# lab1.net
KiCad netlist of a schematic drawn in EAGLE
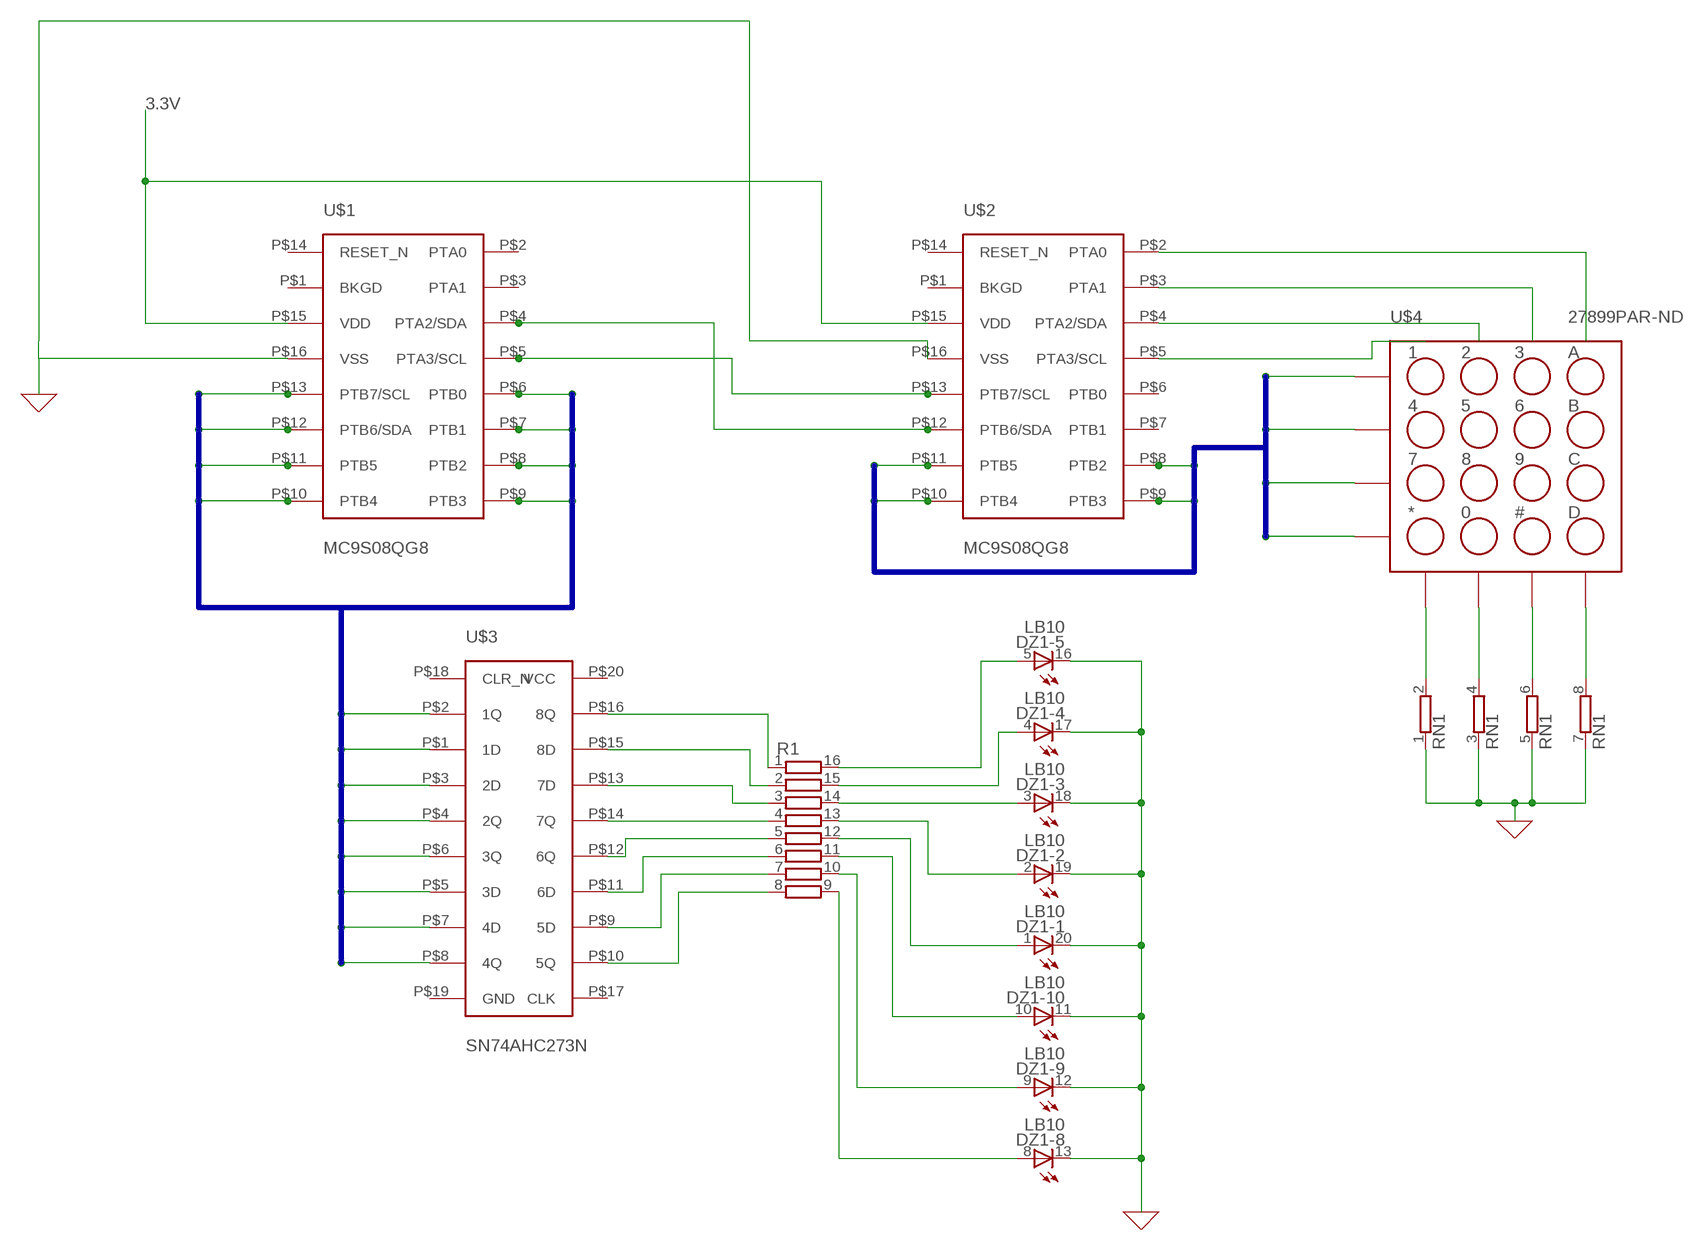
[diagram p0: schematic, sheet 1]

(export (version "E")
  (design (tool "Eeschema 10.0.6"))
  (components
    (comp (ref "DZ1")
      (value "LB10")
      (footprint "eagle-import:LB10")
      (libsource (lib "eagle-import") (part "LB10"))
    )
    (comp (ref "R1")
      (value "2QSP16-8")
      (footprint "eagle-import:2QSP16")
      (libsource (lib "eagle-import") (part "2QSP16-8"))
    )
    (comp (ref "RN1")
      (value "E4RP")
      (footprint "eagle-import:SIL8")
      (libsource (lib "eagle-import") (part "E4RP"))
    )
    (comp (ref "U$1")
      (value "MC9S08QG8")
      (footprint "eagle-import:MC9S08QG8")
      (libsource (lib "eagle-import") (part "MC9S08QG8"))
    )
    (comp (ref "U$2")
      (value "MC9S08QG8")
      (footprint "eagle-import:MC9S08QG8")
      (libsource (lib "eagle-import") (part "MC9S08QG8"))
    )
    (comp (ref "U$3")
      (value "SN74AHC273N")
      (footprint "eagle-import:SN74AHC273N")
      (libsource (lib "eagle-import") (part "SN74AHC273N"))
    )
    (comp (ref "U$4")
      (value "27899PAR-ND")
      (footprint "eagle-import:27899PAR-ND")
      (libsource (lib "eagle-import") (part "27899PAR-ND"))
    )
  )
  (nets
    (net (code "1") (name "/3.3V") (class "Default")
      (node (ref "U$1") (pin "P$15") (pinfunction "VDD_P$15") (pintype "bidirectional"))
      (node (ref "U$2") (pin "P$15") (pinfunction "VDD_P$15") (pintype "bidirectional"))
    )
    (net (code "2") (name "GND") (class "Default")
      (node (ref "DZ1") (pin "11") (pinfunction "C_11") (pintype "passive"))
      (node (ref "DZ1") (pin "12") (pinfunction "C_12") (pintype "passive"))
      (node (ref "DZ1") (pin "13") (pinfunction "C_13") (pintype "passive"))
      (node (ref "DZ1") (pin "16") (pinfunction "C_16") (pintype "passive"))
      (node (ref "DZ1") (pin "17") (pinfunction "C_17") (pintype "passive"))
      (node (ref "DZ1") (pin "18") (pinfunction "C_18") (pintype "passive"))
      (node (ref "DZ1") (pin "19") (pinfunction "C_19") (pintype "passive"))
      (node (ref "DZ1") (pin "20") (pinfunction "C_20") (pintype "passive"))
      (node (ref "RN1") (pin "1") (pinfunction "1_1") (pintype "passive"))
      (node (ref "RN1") (pin "3") (pinfunction "1_3") (pintype "passive"))
      (node (ref "RN1") (pin "5") (pinfunction "1_5") (pintype "passive"))
      (node (ref "RN1") (pin "7") (pinfunction "1_7") (pintype "passive"))
      (node (ref "U$1") (pin "P$16") (pinfunction "VSS_P$16") (pintype "bidirectional"))
      (node (ref "U$2") (pin "P$16") (pinfunction "VSS_P$16") (pintype "bidirectional"))
    )
    (net (code "3") (name "Net-(DZ1A-A)") (class "Default")
      (node (ref "DZ1") (pin "1") (pinfunction "A_1") (pintype "passive"))
      (node (ref "R1") (pin "12") (pinfunction "12_12") (pintype "passive"))
    )
    (net (code "4") (name "Net-(DZ1B-A)") (class "Default")
      (node (ref "DZ1") (pin "10") (pinfunction "A_10") (pintype "passive"))
      (node (ref "R1") (pin "11") (pinfunction "11_11") (pintype "passive"))
    )
    (net (code "5") (name "Net-(DZ1C-A)") (class "Default")
      (node (ref "DZ1") (pin "2") (pinfunction "A_2") (pintype "passive"))
      (node (ref "R1") (pin "13") (pinfunction "13_13") (pintype "passive"))
    )
    (net (code "6") (name "Net-(DZ1D-A)") (class "Default")
      (node (ref "DZ1") (pin "3") (pinfunction "A_3") (pintype "passive"))
      (node (ref "R1") (pin "14") (pinfunction "14_14") (pintype "passive"))
    )
    (net (code "7") (name "Net-(DZ1E-A)") (class "Default")
      (node (ref "DZ1") (pin "4") (pinfunction "A_4") (pintype "passive"))
      (node (ref "R1") (pin "15") (pinfunction "15_15") (pintype "passive"))
    )
    (net (code "8") (name "Net-(DZ1F-A)") (class "Default")
      (node (ref "DZ1") (pin "5") (pinfunction "A_5") (pintype "passive"))
      (node (ref "R1") (pin "16") (pinfunction "16_16") (pintype "passive"))
    )
    (net (code "9") (name "Net-(DZ1I-A)") (class "Default")
      (node (ref "DZ1") (pin "8") (pinfunction "A_8") (pintype "passive"))
      (node (ref "R1") (pin "9") (pinfunction "9_9") (pintype "passive"))
    )
    (net (code "10") (name "Net-(DZ1J-A)") (class "Default")
      (node (ref "DZ1") (pin "9") (pinfunction "A_9") (pintype "passive"))
      (node (ref "R1") (pin "10") (pinfunction "10_10") (pintype "passive"))
    )
    (net (code "11") (name "Net-(RN1-Pad2)") (class "Default")
      (node (ref "RN1") (pin "2") (pinfunction "2_2") (pintype "passive"))
      (node (ref "U$4") (pin "P$8") (pinfunction "P$8_P$8") (pintype "bidirectional"))
    )
    (net (code "12") (name "Net-(RN1B-2)") (class "Default")
      (node (ref "RN1") (pin "4") (pinfunction "2_4") (pintype "passive"))
      (node (ref "U$4") (pin "P$7") (pinfunction "P$7_P$7") (pintype "bidirectional"))
    )
    (net (code "13") (name "Net-(RN1C-2)") (class "Default")
      (node (ref "RN1") (pin "6") (pinfunction "2_6") (pintype "passive"))
      (node (ref "U$4") (pin "P$6") (pinfunction "P$6_P$6") (pintype "bidirectional"))
    )
    (net (code "14") (name "Net-(RN1D-2)") (class "Default")
      (node (ref "RN1") (pin "8") (pinfunction "2_8") (pintype "passive"))
      (node (ref "U$4") (pin "P$5") (pinfunction "P$5_P$5") (pintype "bidirectional"))
    )
    (net (code "15") (name "Net-(U$1-PTA2{slash}SDA)") (class "Default")
      (node (ref "U$1") (pin "P$4") (pinfunction "PTA2/SDA_P$4") (pintype "bidirectional"))
      (node (ref "U$2") (pin "P$12") (pinfunction "PTB6/SDA_P$12") (pintype "bidirectional"))
    )
    (net (code "16") (name "Net-(U$1-PTA3{slash}SCL)") (class "Default")
      (node (ref "U$1") (pin "P$5") (pinfunction "PTA3/SCL_P$5") (pintype "bidirectional"))
      (node (ref "U$2") (pin "P$13") (pinfunction "PTB7/SCL_P$13") (pintype "bidirectional"))
    )
    (net (code "17") (name "Net-(U$3-5D)") (class "Default")
      (node (ref "R1") (pin "7") (pinfunction "7_7") (pintype "passive"))
      (node (ref "U$3") (pin "P$9") (pinfunction "5D_P$9") (pintype "bidirectional"))
    )
    (net (code "18") (name "Net-(U$3-5Q)") (class "Default")
      (node (ref "R1") (pin "8") (pinfunction "8_8") (pintype "passive"))
      (node (ref "U$3") (pin "P$10") (pinfunction "5Q_P$10") (pintype "bidirectional"))
    )
    (net (code "19") (name "Net-(U$3-6D)") (class "Default")
      (node (ref "R1") (pin "6") (pinfunction "6_6") (pintype "passive"))
      (node (ref "U$3") (pin "P$11") (pinfunction "6D_P$11") (pintype "bidirectional"))
    )
    (net (code "20") (name "Net-(U$3-6Q)") (class "Default")
      (node (ref "R1") (pin "5") (pinfunction "5_5") (pintype "passive"))
      (node (ref "U$3") (pin "P$12") (pinfunction "6Q_P$12") (pintype "bidirectional"))
    )
    (net (code "21") (name "Net-(U$3-7D)") (class "Default")
      (node (ref "R1") (pin "3") (pinfunction "3_3") (pintype "passive"))
      (node (ref "U$3") (pin "P$13") (pinfunction "7D_P$13") (pintype "bidirectional"))
    )
    (net (code "22") (name "Net-(U$3-7Q)") (class "Default")
      (node (ref "R1") (pin "4") (pinfunction "4_4") (pintype "passive"))
      (node (ref "U$3") (pin "P$14") (pinfunction "7Q_P$14") (pintype "bidirectional"))
    )
    (net (code "23") (name "Net-(U$3-8D)") (class "Default")
      (node (ref "R1") (pin "2") (pinfunction "2_2") (pintype "passive"))
      (node (ref "U$3") (pin "P$15") (pinfunction "8D_P$15") (pintype "bidirectional"))
    )
    (net (code "24") (name "Net-(U$3-8Q)") (class "Default")
      (node (ref "R1") (pin "1") (pinfunction "1_1") (pintype "passive"))
      (node (ref "U$3") (pin "P$16") (pinfunction "8Q_P$16") (pintype "bidirectional"))
    )
    (net (code "25") (name "unconnected-(U$1-BKGD-PadP$1)") (class "Default")
      (node (ref "U$1") (pin "P$1") (pinfunction "BKGD_P$1") (pintype "bidirectional"))
    )
    (net (code "26") (name "unconnected-(U$1-PTA0-PadP$2)") (class "Default")
      (node (ref "U$1") (pin "P$2") (pinfunction "PTA0_P$2") (pintype "bidirectional"))
    )
    (net (code "27") (name "unconnected-(U$1-PTA1-PadP$3)") (class "Default")
      (node (ref "U$1") (pin "P$3") (pinfunction "PTA1_P$3") (pintype "bidirectional"))
    )
    (net (code "28") (name "unconnected-(U$1-PTB0-PadP$6)") (class "Default")
      (node (ref "U$1") (pin "P$6") (pinfunction "PTB0_P$6") (pintype "bidirectional"))
    )
    (net (code "29") (name "unconnected-(U$1-PTB1-PadP$7)") (class "Default")
      (node (ref "U$1") (pin "P$7") (pinfunction "PTB1_P$7") (pintype "bidirectional"))
    )
    (net (code "30") (name "unconnected-(U$1-PTB2-PadP$8)") (class "Default")
      (node (ref "U$1") (pin "P$8") (pinfunction "PTB2_P$8") (pintype "bidirectional"))
    )
    (net (code "31") (name "unconnected-(U$1-PTB3-PadP$9)") (class "Default")
      (node (ref "U$1") (pin "P$9") (pinfunction "PTB3_P$9") (pintype "bidirectional"))
    )
    (net (code "32") (name "unconnected-(U$1-PTB4-PadP$10)") (class "Default")
      (node (ref "U$1") (pin "P$10") (pinfunction "PTB4_P$10") (pintype "bidirectional"))
    )
    (net (code "33") (name "unconnected-(U$1-PTB5-PadP$11)") (class "Default")
      (node (ref "U$1") (pin "P$11") (pinfunction "PTB5_P$11") (pintype "bidirectional"))
    )
    (net (code "34") (name "unconnected-(U$1-PTB6{slash}SDA-PadP$12)") (class "Default")
      (node (ref "U$1") (pin "P$12") (pinfunction "PTB6/SDA_P$12") (pintype "bidirectional"))
    )
    (net (code "35") (name "unconnected-(U$1-PTB7{slash}SCL-PadP$13)") (class "Default")
      (node (ref "U$1") (pin "P$13") (pinfunction "PTB7/SCL_P$13") (pintype "bidirectional"))
    )
    (net (code "36") (name "unconnected-(U$1-RESET_N-PadP$14)") (class "Default")
      (node (ref "U$1") (pin "P$14") (pinfunction "RESET_N_P$14") (pintype "bidirectional"))
    )
    (net (code "37") (name "unconnected-(U$2-BKGD-PadP$1)") (class "Default")
      (node (ref "U$2") (pin "P$1") (pinfunction "BKGD_P$1") (pintype "bidirectional"))
    )
    (net (code "38") (name "unconnected-(U$2-PTA0-PadP$2)") (class "Default")
      (node (ref "U$2") (pin "P$2") (pinfunction "PTA0_P$2") (pintype "bidirectional"))
    )
    (net (code "39") (name "unconnected-(U$2-PTA1-PadP$3)") (class "Default")
      (node (ref "U$2") (pin "P$3") (pinfunction "PTA1_P$3") (pintype "bidirectional"))
    )
    (net (code "40") (name "unconnected-(U$2-PTA2{slash}SDA-PadP$4)") (class "Default")
      (node (ref "U$2") (pin "P$4") (pinfunction "PTA2/SDA_P$4") (pintype "bidirectional"))
    )
    (net (code "41") (name "unconnected-(U$2-PTA3{slash}SCL-PadP$5)") (class "Default")
      (node (ref "U$2") (pin "P$5") (pinfunction "PTA3/SCL_P$5") (pintype "bidirectional"))
    )
    (net (code "42") (name "unconnected-(U$2-PTB0-PadP$6)") (class "Default")
      (node (ref "U$2") (pin "P$6") (pinfunction "PTB0_P$6") (pintype "bidirectional"))
    )
    (net (code "43") (name "unconnected-(U$2-PTB1-PadP$7)") (class "Default")
      (node (ref "U$2") (pin "P$7") (pinfunction "PTB1_P$7") (pintype "bidirectional"))
    )
    (net (code "44") (name "unconnected-(U$2-PTB2-PadP$8)") (class "Default")
      (node (ref "U$2") (pin "P$8") (pinfunction "PTB2_P$8") (pintype "bidirectional"))
    )
    (net (code "45") (name "unconnected-(U$2-PTB3-PadP$9)") (class "Default")
      (node (ref "U$2") (pin "P$9") (pinfunction "PTB3_P$9") (pintype "bidirectional"))
    )
    (net (code "46") (name "unconnected-(U$2-PTB4-PadP$10)") (class "Default")
      (node (ref "U$2") (pin "P$10") (pinfunction "PTB4_P$10") (pintype "bidirectional"))
    )
    (net (code "47") (name "unconnected-(U$2-PTB5-PadP$11)") (class "Default")
      (node (ref "U$2") (pin "P$11") (pinfunction "PTB5_P$11") (pintype "bidirectional"))
    )
    (net (code "48") (name "unconnected-(U$2-RESET_N-PadP$14)") (class "Default")
      (node (ref "U$2") (pin "P$14") (pinfunction "RESET_N_P$14") (pintype "bidirectional"))
    )
    (net (code "49") (name "unconnected-(U$3-1D-PadP$1)") (class "Default")
      (node (ref "U$3") (pin "P$1") (pinfunction "1D_P$1") (pintype "bidirectional"))
    )
    (net (code "50") (name "unconnected-(U$3-1Q-PadP$2)") (class "Default")
      (node (ref "U$3") (pin "P$2") (pinfunction "1Q_P$2") (pintype "bidirectional"))
    )
    (net (code "51") (name "unconnected-(U$3-2D-PadP$3)") (class "Default")
      (node (ref "U$3") (pin "P$3") (pinfunction "2D_P$3") (pintype "bidirectional"))
    )
    (net (code "52") (name "unconnected-(U$3-2Q-PadP$4)") (class "Default")
      (node (ref "U$3") (pin "P$4") (pinfunction "2Q_P$4") (pintype "bidirectional"))
    )
    (net (code "53") (name "unconnected-(U$3-3D-PadP$5)") (class "Default")
      (node (ref "U$3") (pin "P$5") (pinfunction "3D_P$5") (pintype "bidirectional"))
    )
    (net (code "54") (name "unconnected-(U$3-3Q-PadP$6)") (class "Default")
      (node (ref "U$3") (pin "P$6") (pinfunction "3Q_P$6") (pintype "bidirectional"))
    )
    (net (code "55") (name "unconnected-(U$3-4D-PadP$7)") (class "Default")
      (node (ref "U$3") (pin "P$7") (pinfunction "4D_P$7") (pintype "bidirectional"))
    )
    (net (code "56") (name "unconnected-(U$3-4Q-PadP$8)") (class "Default")
      (node (ref "U$3") (pin "P$8") (pinfunction "4Q_P$8") (pintype "bidirectional"))
    )
    (net (code "57") (name "unconnected-(U$3-CLK-PadP$17)") (class "Default")
      (node (ref "U$3") (pin "P$17") (pinfunction "CLK_P$17") (pintype "bidirectional"))
    )
    (net (code "58") (name "unconnected-(U$3-CLR_N-PadP$18)") (class "Default")
      (node (ref "U$3") (pin "P$18") (pinfunction "CLR_N_P$18") (pintype "bidirectional"))
    )
    (net (code "59") (name "unconnected-(U$3-GND-PadP$19)") (class "Default")
      (node (ref "U$3") (pin "P$19") (pinfunction "GND_P$19") (pintype "bidirectional"))
    )
    (net (code "60") (name "unconnected-(U$3-VCC-PadP$20)") (class "Default")
      (node (ref "U$3") (pin "P$20") (pinfunction "VCC_P$20") (pintype "bidirectional"))
    )
    (net (code "61") (name "unconnected-(U$4-PadP$1)") (class "Default")
      (node (ref "U$4") (pin "P$1") (pinfunction "P$1_P$1") (pintype "bidirectional"))
    )
    (net (code "62") (name "unconnected-(U$4-PadP$2)") (class "Default")
      (node (ref "U$4") (pin "P$2") (pinfunction "P$2_P$2") (pintype "bidirectional"))
    )
    (net (code "63") (name "unconnected-(U$4-PadP$3)") (class "Default")
      (node (ref "U$4") (pin "P$3") (pinfunction "P$3_P$3") (pintype "bidirectional"))
    )
    (net (code "64") (name "unconnected-(U$4-PadP$4)") (class "Default")
      (node (ref "U$4") (pin "P$4") (pinfunction "P$4_P$4") (pintype "bidirectional"))
    )
  )
)
